# Word_Clock.net
KiCad netlist of a schematic drawn in EAGLE
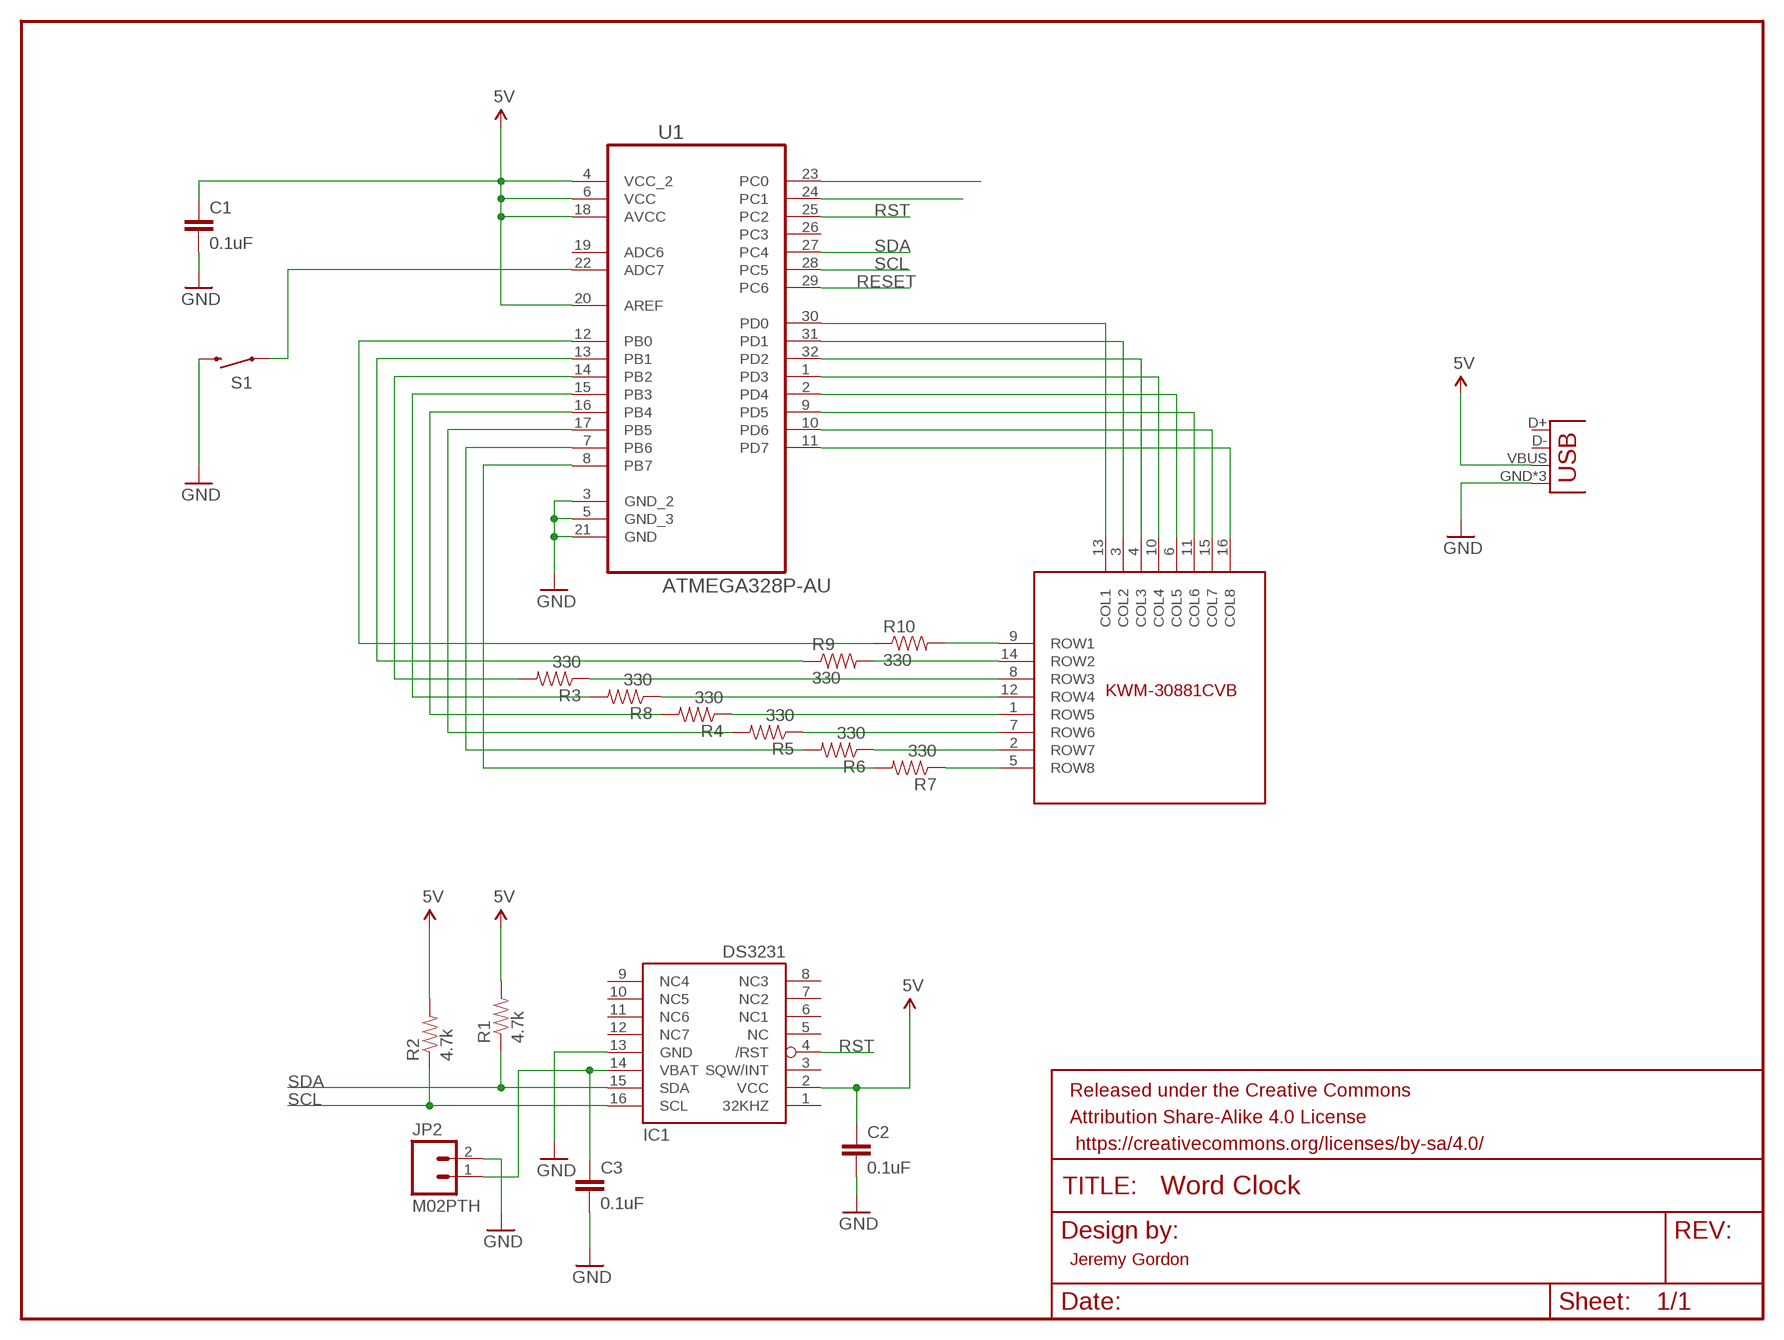
[diagram p0: schematic, sheet 1]

(export (version "E")
  (design (tool "Eeschema 10.0.6"))
  (components
    (comp (ref "C1")
      (value "0.1uF")
      (footprint "eagle-import:0805")
      (libsource (lib "eagle-import") (part "CAP0805"))
    )
    (comp (ref "C2")
      (value "0.1uF")
      (footprint "eagle-import:0805")
      (libsource (lib "eagle-import") (part "CAP0805"))
    )
    (comp (ref "C3")
      (value "0.1uF")
      (footprint "eagle-import:0805")
      (libsource (lib "eagle-import") (part "CAP0805"))
    )
    (comp (ref "D1")
      (value "KWM-30881CVB")
      (footprint "eagle-import:KWM-30881CVB")
      (libsource (lib "eagle-import") (part "KWM-30881CVB"))
    )
    (comp (ref "FRAME1")
      (value "FRAME-LETTER")
      (footprint "eagle-import:CREATIVE_COMMONS")
      (libsource (lib "eagle-import") (part "FRAME-LETTER"))
    )
    (comp (ref "IC1")
      (value "DS3231/SO")
      (footprint "eagle-import:SO16W")
      (libsource (lib "eagle-import") (part "DS3231/SO"))
    )
    (comp (ref "JP1")
      (value "USB-MICROB")
      (footprint "eagle-import:USB-MICROB")
      (libsource (lib "eagle-import") (part "USB-MICROB"))
    )
    (comp (ref "JP2")
      (value "M02PTH")
      (footprint "eagle-import:1X02")
      (libsource (lib "eagle-import") (part "M02PTH"))
    )
    (comp (ref "R1")
      (value "4.7k")
      (footprint "eagle-import:0805")
      (libsource (lib "eagle-import") (part "RESISTOR0805-RES"))
    )
    (comp (ref "R2")
      (value "4.7k")
      (footprint "eagle-import:0805")
      (libsource (lib "eagle-import") (part "RESISTOR0805-RES"))
    )
    (comp (ref "R3")
      (value "330")
      (footprint "eagle-import:0805")
      (libsource (lib "eagle-import") (part "RESISTOR0805-RES"))
    )
    (comp (ref "R4")
      (value "330")
      (footprint "eagle-import:0805")
      (libsource (lib "eagle-import") (part "RESISTOR0805-RES"))
    )
    (comp (ref "R5")
      (value "330")
      (footprint "eagle-import:0805")
      (libsource (lib "eagle-import") (part "RESISTOR0805-RES"))
    )
    (comp (ref "R6")
      (value "330")
      (footprint "eagle-import:0805")
      (libsource (lib "eagle-import") (part "RESISTOR0805-RES"))
    )
    (comp (ref "R7")
      (value "330")
      (footprint "eagle-import:0805")
      (libsource (lib "eagle-import") (part "RESISTOR0805-RES"))
    )
    (comp (ref "R8")
      (value "330")
      (footprint "eagle-import:0805")
      (libsource (lib "eagle-import") (part "RESISTOR0805-RES"))
    )
    (comp (ref "R9")
      (value "330")
      (footprint "eagle-import:0805")
      (libsource (lib "eagle-import") (part "RESISTOR0805-RES"))
    )
    (comp (ref "R10")
      (value "330")
      (footprint "eagle-import:0805")
      (libsource (lib "eagle-import") (part "RESISTOR0805-RES"))
    )
    (comp (ref "S1")
      (value "SWITCH-MOMENTARY-2SMD-1101NE")
      (footprint "eagle-import:TACTILE-SWITCH-1101NE")
      (libsource (lib "eagle-import") (part "SWITCH-MOMENTARY-2SMD-1101NE"))
    )
    (comp (ref "U1")
      (value "ATMEGA328P-AU")
      (footprint "eagle-import:QFP80P900X900X120-32N")
      (libsource (lib "eagle-import") (part "ATMEGA328P-AU"))
    )
  )
  (nets
    (net (code "1") (name "/RESET") (class "Default")
      (node (ref "U1") (pin "29") (pinfunction "PC6_29") (pintype "bidirectional"))
    )
    (net (code "2") (name "/RST") (class "Default")
      (node (ref "IC1") (pin "4") (pinfunction "/RST_4") (pintype "passive"))
      (node (ref "U1") (pin "25") (pinfunction "PC2_25") (pintype "bidirectional"))
    )
    (net (code "3") (name "/SCL") (class "Default")
      (node (ref "IC1") (pin "16") (pinfunction "SCL_16") (pintype "bidirectional"))
      (node (ref "R2") (pin "1") (pinfunction "1_1") (pintype "passive"))
      (node (ref "U1") (pin "28") (pinfunction "PC5_28") (pintype "bidirectional"))
    )
    (net (code "4") (name "/SDA") (class "Default")
      (node (ref "IC1") (pin "15") (pinfunction "SDA_15") (pintype "bidirectional"))
      (node (ref "R1") (pin "1") (pinfunction "1_1") (pintype "passive"))
      (node (ref "U1") (pin "27") (pinfunction "PC4_27") (pintype "bidirectional"))
    )
    (net (code "5") (name "5V") (class "Default")
      (node (ref "C1") (pin "1") (pinfunction "1_1") (pintype "passive"))
      (node (ref "C2") (pin "1") (pinfunction "1_1") (pintype "passive"))
      (node (ref "IC1") (pin "2") (pinfunction "VCC_2") (pintype "power_in"))
      (node (ref "JP1") (pin "VBUS") (pinfunction "VBUS_VBUS") (pintype "bidirectional"))
      (node (ref "R1") (pin "2") (pinfunction "2_2") (pintype "passive"))
      (node (ref "R2") (pin "2") (pinfunction "2_2") (pintype "passive"))
      (node (ref "U1") (pin "18") (pinfunction "AVCC_18") (pintype "power_in"))
      (node (ref "U1") (pin "20") (pinfunction "AREF_20") (pintype "input"))
      (node (ref "U1") (pin "4") (pinfunction "VCC_2_4") (pintype "power_in"))
      (node (ref "U1") (pin "6") (pinfunction "VCC_6") (pintype "power_in"))
    )
    (net (code "6") (name "GND") (class "Default")
      (node (ref "C1") (pin "2") (pinfunction "2_2") (pintype "passive"))
      (node (ref "C2") (pin "2") (pinfunction "2_2") (pintype "passive"))
      (node (ref "C3") (pin "2") (pinfunction "2_2") (pintype "passive"))
      (node (ref "IC1") (pin "13") (pinfunction "GND_13") (pintype "power_in"))
      (node (ref "JP1") (pin "GND") (pinfunction "GND_GND") (pintype "bidirectional"))
      (node (ref "JP1") (pin "MT1") (pinfunction "GND_MT1") (pintype "bidirectional"))
      (node (ref "JP1") (pin "MT2") (pinfunction "GND_MT2") (pintype "bidirectional"))
      (node (ref "JP2") (pin "2") (pinfunction "2_2") (pintype "passive"))
      (node (ref "S1") (pin "2") (pinfunction "2_2") (pintype "passive"))
      (node (ref "U1") (pin "21") (pinfunction "GND_21") (pintype "passive"))
      (node (ref "U1") (pin "3") (pinfunction "GND_2_3") (pintype "passive"))
      (node (ref "U1") (pin "5") (pinfunction "GND_3_5") (pintype "passive"))
    )
    (net (code "7") (name "Net-(D1-COL1)") (class "Default")
      (node (ref "D1") (pin "13") (pinfunction "COL1_13") (pintype "bidirectional"))
      (node (ref "U1") (pin "30") (pinfunction "PD0_30") (pintype "bidirectional"))
    )
    (net (code "8") (name "Net-(D1-COL2)") (class "Default")
      (node (ref "D1") (pin "3") (pinfunction "COL2_3") (pintype "bidirectional"))
      (node (ref "U1") (pin "31") (pinfunction "PD1_31") (pintype "bidirectional"))
    )
    (net (code "9") (name "Net-(D1-COL3)") (class "Default")
      (node (ref "D1") (pin "4") (pinfunction "COL3_4") (pintype "bidirectional"))
      (node (ref "U1") (pin "32") (pinfunction "PD2_32") (pintype "bidirectional"))
    )
    (net (code "10") (name "Net-(D1-COL4)") (class "Default")
      (node (ref "D1") (pin "10") (pinfunction "COL4_10") (pintype "bidirectional"))
      (node (ref "U1") (pin "1") (pinfunction "PD3_1") (pintype "bidirectional"))
    )
    (net (code "11") (name "Net-(D1-COL5)") (class "Default")
      (node (ref "D1") (pin "6") (pinfunction "COL5_6") (pintype "bidirectional"))
      (node (ref "U1") (pin "2") (pinfunction "PD4_2") (pintype "bidirectional"))
    )
    (net (code "12") (name "Net-(D1-COL6)") (class "Default")
      (node (ref "D1") (pin "11") (pinfunction "COL6_11") (pintype "bidirectional"))
      (node (ref "U1") (pin "9") (pinfunction "PD5_9") (pintype "bidirectional"))
    )
    (net (code "13") (name "Net-(D1-COL7)") (class "Default")
      (node (ref "D1") (pin "15") (pinfunction "COL7_15") (pintype "bidirectional"))
      (node (ref "U1") (pin "10") (pinfunction "PD6_10") (pintype "bidirectional"))
    )
    (net (code "14") (name "Net-(D1-COL8)") (class "Default")
      (node (ref "D1") (pin "16") (pinfunction "COL8_16") (pintype "bidirectional"))
      (node (ref "U1") (pin "11") (pinfunction "PD7_11") (pintype "bidirectional"))
    )
    (net (code "15") (name "Net-(D1-ROW1)") (class "Default")
      (node (ref "D1") (pin "9") (pinfunction "ROW1_9") (pintype "bidirectional"))
      (node (ref "R10") (pin "2") (pinfunction "2_2") (pintype "passive"))
    )
    (net (code "16") (name "Net-(D1-ROW2)") (class "Default")
      (node (ref "D1") (pin "14") (pinfunction "ROW2_14") (pintype "bidirectional"))
      (node (ref "R9") (pin "2") (pinfunction "2_2") (pintype "passive"))
    )
    (net (code "17") (name "Net-(D1-ROW3)") (class "Default")
      (node (ref "D1") (pin "8") (pinfunction "ROW3_8") (pintype "bidirectional"))
      (node (ref "R3") (pin "1") (pinfunction "1_1") (pintype "passive"))
    )
    (net (code "18") (name "Net-(D1-ROW4)") (class "Default")
      (node (ref "D1") (pin "12") (pinfunction "ROW4_12") (pintype "bidirectional"))
      (node (ref "R8") (pin "1") (pinfunction "1_1") (pintype "passive"))
    )
    (net (code "19") (name "Net-(D1-ROW5)") (class "Default")
      (node (ref "D1") (pin "1") (pinfunction "ROW5_1") (pintype "bidirectional"))
      (node (ref "R4") (pin "1") (pinfunction "1_1") (pintype "passive"))
    )
    (net (code "20") (name "Net-(D1-ROW6)") (class "Default")
      (node (ref "D1") (pin "7") (pinfunction "ROW6_7") (pintype "bidirectional"))
      (node (ref "R5") (pin "1") (pinfunction "1_1") (pintype "passive"))
    )
    (net (code "21") (name "Net-(D1-ROW7)") (class "Default")
      (node (ref "D1") (pin "2") (pinfunction "ROW7_2") (pintype "bidirectional"))
      (node (ref "R6") (pin "1") (pinfunction "1_1") (pintype "passive"))
    )
    (net (code "22") (name "Net-(D1-ROW8)") (class "Default")
      (node (ref "D1") (pin "5") (pinfunction "ROW8_5") (pintype "bidirectional"))
      (node (ref "R7") (pin "1") (pinfunction "1_1") (pintype "passive"))
    )
    (net (code "23") (name "Net-(IC1-VBAT)") (class "Default")
      (node (ref "C3") (pin "1") (pinfunction "1_1") (pintype "passive"))
      (node (ref "IC1") (pin "14") (pinfunction "VBAT_14") (pintype "power_in"))
      (node (ref "JP2") (pin "1") (pinfunction "1_1") (pintype "passive"))
    )
    (net (code "24") (name "Net-(U1-ADC7)") (class "Default")
      (node (ref "S1") (pin "1") (pinfunction "1_1") (pintype "passive"))
      (node (ref "U1") (pin "22") (pinfunction "ADC7_22") (pintype "input"))
    )
    (net (code "25") (name "Net-(U1-PB0)") (class "Default")
      (node (ref "R10") (pin "1") (pinfunction "1_1") (pintype "passive"))
      (node (ref "U1") (pin "12") (pinfunction "PB0_12") (pintype "bidirectional"))
    )
    (net (code "26") (name "Net-(U1-PB1)") (class "Default")
      (node (ref "R9") (pin "1") (pinfunction "1_1") (pintype "passive"))
      (node (ref "U1") (pin "13") (pinfunction "PB1_13") (pintype "bidirectional"))
    )
    (net (code "27") (name "Net-(U1-PB2)") (class "Default")
      (node (ref "R3") (pin "2") (pinfunction "2_2") (pintype "passive"))
      (node (ref "U1") (pin "14") (pinfunction "PB2_14") (pintype "bidirectional"))
    )
    (net (code "28") (name "Net-(U1-PB3)") (class "Default")
      (node (ref "R8") (pin "2") (pinfunction "2_2") (pintype "passive"))
      (node (ref "U1") (pin "15") (pinfunction "PB3_15") (pintype "bidirectional"))
    )
    (net (code "29") (name "Net-(U1-PB4)") (class "Default")
      (node (ref "R4") (pin "2") (pinfunction "2_2") (pintype "passive"))
      (node (ref "U1") (pin "16") (pinfunction "PB4_16") (pintype "bidirectional"))
    )
    (net (code "30") (name "Net-(U1-PB5)") (class "Default")
      (node (ref "R5") (pin "2") (pinfunction "2_2") (pintype "passive"))
      (node (ref "U1") (pin "17") (pinfunction "PB5_17") (pintype "bidirectional"))
    )
    (net (code "31") (name "Net-(U1-PB6)") (class "Default")
      (node (ref "R6") (pin "2") (pinfunction "2_2") (pintype "passive"))
      (node (ref "U1") (pin "7") (pinfunction "PB6_7") (pintype "bidirectional"))
    )
    (net (code "32") (name "Net-(U1-PB7)") (class "Default")
      (node (ref "R7") (pin "2") (pinfunction "2_2") (pintype "passive"))
      (node (ref "U1") (pin "8") (pinfunction "PB7_8") (pintype "bidirectional"))
    )
    (net (code "33") (name "unconnected-(IC1-32KHZ-Pad1)") (class "Default")
      (node (ref "IC1") (pin "1") (pinfunction "32KHZ_1") (pintype "output"))
    )
    (net (code "34") (name "unconnected-(IC1-NC-Pad5)") (class "Default")
      (node (ref "IC1") (pin "5") (pinfunction "NC_5") (pintype "no_connect"))
    )
    (net (code "35") (name "unconnected-(IC1-NC1-Pad6)") (class "Default")
      (node (ref "IC1") (pin "6") (pinfunction "NC1_6") (pintype "no_connect"))
    )
    (net (code "36") (name "unconnected-(IC1-NC2-Pad7)") (class "Default")
      (node (ref "IC1") (pin "7") (pinfunction "NC2_7") (pintype "no_connect"))
    )
    (net (code "37") (name "unconnected-(IC1-NC3-Pad8)") (class "Default")
      (node (ref "IC1") (pin "8") (pinfunction "NC3_8") (pintype "no_connect"))
    )
    (net (code "38") (name "unconnected-(IC1-NC4-Pad9)") (class "Default")
      (node (ref "IC1") (pin "9") (pinfunction "NC4_9") (pintype "no_connect"))
    )
    (net (code "39") (name "unconnected-(IC1-NC5-Pad10)") (class "Default")
      (node (ref "IC1") (pin "10") (pinfunction "NC5_10") (pintype "no_connect"))
    )
    (net (code "40") (name "unconnected-(IC1-NC6-Pad11)") (class "Default")
      (node (ref "IC1") (pin "11") (pinfunction "NC6_11") (pintype "no_connect"))
    )
    (net (code "41") (name "unconnected-(IC1-NC7-Pad12)") (class "Default")
      (node (ref "IC1") (pin "12") (pinfunction "NC7_12") (pintype "no_connect"))
    )
    (net (code "42") (name "unconnected-(IC1-SQW{slash}INT-Pad3)") (class "Default")
      (node (ref "IC1") (pin "3") (pinfunction "SQW/INT_3") (pintype "output"))
    )
    (net (code "43") (name "unconnected-(JP1-PadD+)") (class "Default")
      (node (ref "JP1") (pin "D+") (pinfunction "D+_D+") (pintype "bidirectional"))
    )
    (net (code "44") (name "unconnected-(JP1-PadD-)") (class "Default")
      (node (ref "JP1") (pin "D-") (pinfunction "D-_D-") (pintype "bidirectional"))
    )
    (net (code "45") (name "unconnected-(U1-ADC6-Pad19)") (class "Default")
      (node (ref "U1") (pin "19") (pinfunction "ADC6_19") (pintype "input"))
    )
    (net (code "46") (name "unconnected-(U1-PC0-Pad23)") (class "Default")
      (node (ref "U1") (pin "23") (pinfunction "PC0_23") (pintype "bidirectional"))
    )
    (net (code "47") (name "unconnected-(U1-PC1-Pad24)") (class "Default")
      (node (ref "U1") (pin "24") (pinfunction "PC1_24") (pintype "bidirectional"))
    )
    (net (code "48") (name "unconnected-(U1-PC3-Pad26)") (class "Default")
      (node (ref "U1") (pin "26") (pinfunction "PC3_26") (pintype "bidirectional"))
    )
  )
)
